# EfBox_v1.net
KiCad netlist of a schematic drawn in EAGLE
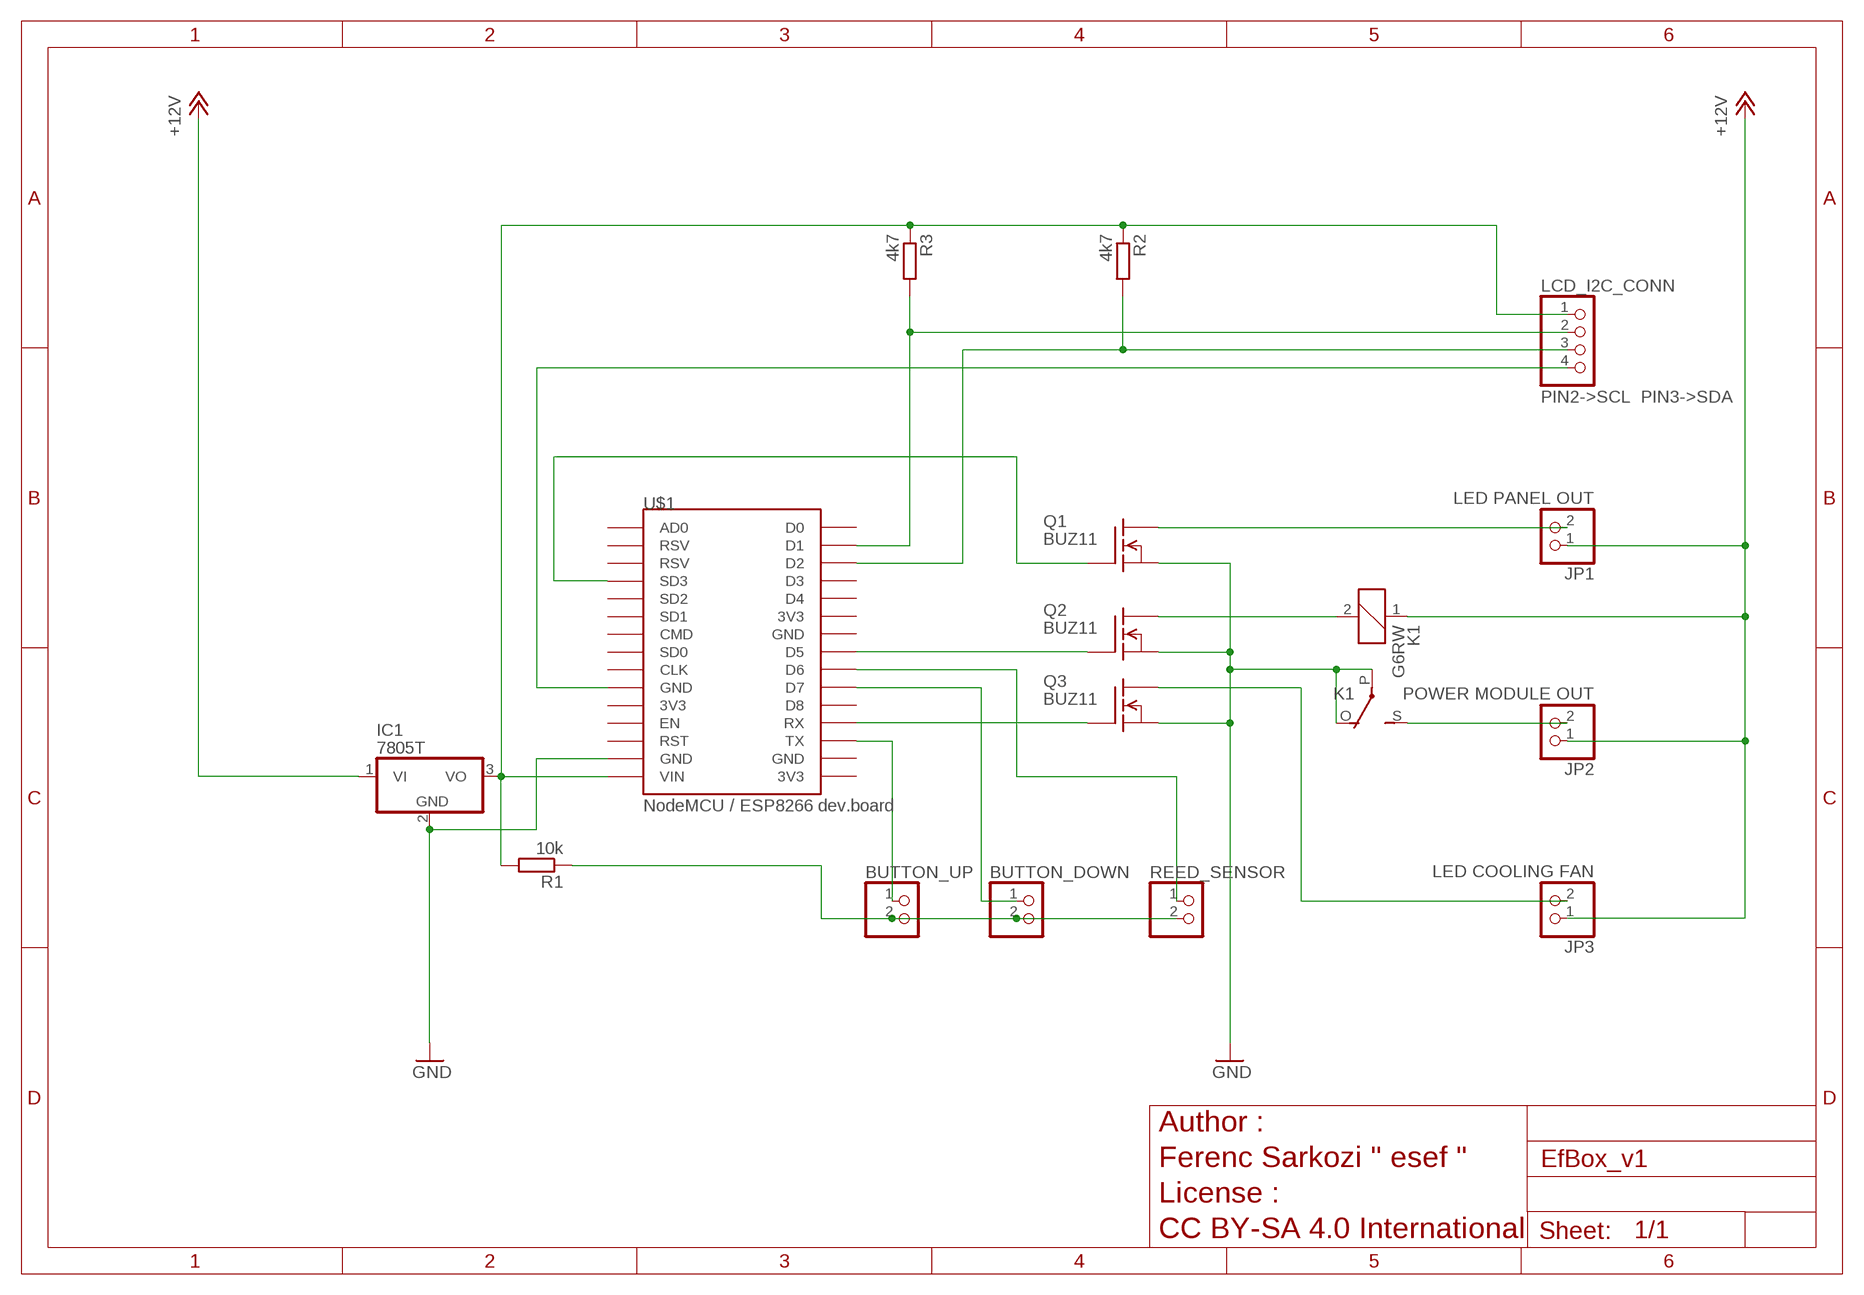
[diagram p0: schematic, sheet 1]

(export (version "E")
  (design (tool "Eeschema 10.0.6"))
  (components
    (comp (ref "BUTTON_DOWN")
      (value "PINHD-1X2")
      (footprint "eagle-import:1X02")
      (libsource (lib "eagle-import") (part "PINHD-1X2"))
    )
    (comp (ref "BUTTON_UP")
      (value "PINHD-1X2")
      (footprint "eagle-import:1X02")
      (libsource (lib "eagle-import") (part "PINHD-1X2"))
    )
    (comp (ref "IC1")
      (value "7805T")
      (footprint "eagle-import:TO220H")
      (libsource (lib "eagle-import") (part "78T05"))
    )
    (comp (ref "JP1")
      (value "LED PANEL OUT")
      (footprint "eagle-import:1X02")
      (libsource (lib "eagle-import") (part "PINHD-1X2"))
    )
    (comp (ref "JP2")
      (value "POWER MODULE OUT")
      (footprint "eagle-import:1X02")
      (libsource (lib "eagle-import") (part "PINHD-1X2"))
    )
    (comp (ref "JP3")
      (value "LED COOLING FAN")
      (footprint "eagle-import:1X02")
      (libsource (lib "eagle-import") (part "PINHD-1X2"))
    )
    (comp (ref "K1")
      (value "G6RW")
      (footprint "eagle-import:G6RW")
      (libsource (lib "eagle-import") (part "G6RW"))
    )
    (comp (ref "LCD_I2C_CONN")
      (value "PIN2->SCL PIN3->SDA")
      (footprint "eagle-import:1X04")
      (libsource (lib "eagle-import") (part "PINHD-1X4"))
    )
    (comp (ref "Q1")
      (value "BUZ11")
      (footprint "eagle-import:TO220")
      (libsource (lib "eagle-import") (part "BUZ11"))
    )
    (comp (ref "Q2")
      (value "BUZ11")
      (footprint "eagle-import:TO220")
      (libsource (lib "eagle-import") (part "BUZ11"))
    )
    (comp (ref "Q3")
      (value "BUZ11")
      (footprint "eagle-import:TO220")
      (libsource (lib "eagle-import") (part "BUZ11"))
    )
    (comp (ref "R1")
      (value "10k")
      (footprint "eagle-import:0411_12")
      (libsource (lib "eagle-import") (part "R-EU_0411/12"))
    )
    (comp (ref "R2")
      (value "4k7")
      (footprint "eagle-import:0411_12")
      (libsource (lib "eagle-import") (part "R-EU_0411/12"))
    )
    (comp (ref "R3")
      (value "4k7")
      (footprint "eagle-import:0411_12")
      (libsource (lib "eagle-import") (part "R-EU_0411/12"))
    )
    (comp (ref "REED_SENSOR")
      (value "PINHD-1X2")
      (footprint "eagle-import:1X02")
      (libsource (lib "eagle-import") (part "PINHD-1X2"))
    )
    (comp (ref "U$1")
      (value "NodeMCU / ESP8266 dev.board")
      (footprint "eagle-import:ESP12E_DEVKIT")
      (libsource (lib "eagle-import") (part "ESP12E_DEVKIT"))
    )
  )
  (nets
    (net (code "1") (name "+12V") (class "Default")
      (node (ref "IC1") (pin "1") (pinfunction "VI_1") (pintype "input"))
      (node (ref "JP1") (pin "1") (pinfunction "1_1") (pintype "passive"))
      (node (ref "JP2") (pin "1") (pinfunction "1_1") (pintype "passive"))
      (node (ref "JP3") (pin "1") (pinfunction "1_1") (pintype "passive"))
      (node (ref "K1") (pin "1") (pinfunction "1_1") (pintype "passive"))
    )
    (net (code "2") (name "GND") (class "Default")
      (node (ref "IC1") (pin "2") (pinfunction "GND_2") (pintype "passive"))
      (node (ref "K1") (pin "O") (pinfunction "O_O") (pintype "passive"))
      (node (ref "K1") (pin "P") (pinfunction "P_P") (pintype "passive"))
      (node (ref "Q1") (pin "3") (pinfunction "S_3") (pintype "passive"))
      (node (ref "Q2") (pin "3") (pinfunction "S_3") (pintype "passive"))
      (node (ref "Q3") (pin "3") (pinfunction "S_3") (pintype "passive"))
      (node (ref "U$1") (pin "GND@1") (pinfunction "GND_GND@1") (pintype "bidirectional"))
    )
    (net (code "3") (name "Net-(BUTTON_DOWN-Pad1)") (class "Default")
      (node (ref "BUTTON_DOWN") (pin "1") (pinfunction "1_1") (pintype "passive"))
      (node (ref "U$1") (pin "D7") (pinfunction "D7_D7") (pintype "bidirectional"))
    )
    (net (code "4") (name "Net-(BUTTON_DOWN-Pad2)") (class "Default")
      (node (ref "BUTTON_DOWN") (pin "2") (pinfunction "2_2") (pintype "passive"))
      (node (ref "BUTTON_UP") (pin "2") (pinfunction "2_2") (pintype "passive"))
      (node (ref "R1") (pin "1") (pinfunction "1_1") (pintype "passive"))
      (node (ref "REED_SENSOR") (pin "2") (pinfunction "2_2") (pintype "passive"))
    )
    (net (code "5") (name "Net-(BUTTON_UP-Pad1)") (class "Default")
      (node (ref "BUTTON_UP") (pin "1") (pinfunction "1_1") (pintype "passive"))
      (node (ref "U$1") (pin "TX") (pinfunction "TX_TX") (pintype "bidirectional"))
    )
    (net (code "6") (name "Net-(IC1-VO)") (class "Default")
      (node (ref "IC1") (pin "3") (pinfunction "VO_3") (pintype "passive"))
      (node (ref "LCD_I2C_CONN") (pin "1") (pinfunction "1_1") (pintype "passive"))
      (node (ref "R1") (pin "2") (pinfunction "2_2") (pintype "passive"))
      (node (ref "R2") (pin "1") (pinfunction "1_1") (pintype "passive"))
      (node (ref "R3") (pin "1") (pinfunction "1_1") (pintype "passive"))
      (node (ref "U$1") (pin "VIN") (pinfunction "VIN_VIN") (pintype "bidirectional"))
    )
    (net (code "7") (name "Net-(JP2-Pad2)") (class "Default")
      (node (ref "JP2") (pin "2") (pinfunction "2_2") (pintype "passive"))
      (node (ref "K1") (pin "S") (pinfunction "S_S") (pintype "passive"))
    )
    (net (code "8") (name "Net-(LCD_I2C_CONN-Pad2)") (class "Default")
      (node (ref "LCD_I2C_CONN") (pin "2") (pinfunction "2_2") (pintype "passive"))
      (node (ref "R3") (pin "2") (pinfunction "2_2") (pintype "passive"))
      (node (ref "U$1") (pin "D1") (pinfunction "D1_D1") (pintype "bidirectional"))
    )
    (net (code "9") (name "Net-(LCD_I2C_CONN-Pad3)") (class "Default")
      (node (ref "LCD_I2C_CONN") (pin "3") (pinfunction "3_3") (pintype "passive"))
      (node (ref "R2") (pin "2") (pinfunction "2_2") (pintype "passive"))
      (node (ref "U$1") (pin "D2") (pinfunction "D2_D2") (pintype "bidirectional"))
    )
    (net (code "10") (name "Net-(LCD_I2C_CONN-Pad4)") (class "Default")
      (node (ref "LCD_I2C_CONN") (pin "4") (pinfunction "4_4") (pintype "passive"))
      (node (ref "U$1") (pin "GND@0") (pinfunction "GND_GND@0") (pintype "bidirectional"))
    )
    (net (code "11") (name "Net-(Q1-D)") (class "Default")
      (node (ref "JP1") (pin "2") (pinfunction "2_2") (pintype "passive"))
      (node (ref "Q1") (pin "2") (pinfunction "D_2") (pintype "passive"))
    )
    (net (code "12") (name "Net-(Q1-G)") (class "Default")
      (node (ref "Q1") (pin "1") (pinfunction "G_1") (pintype "passive"))
      (node (ref "U$1") (pin "SD3") (pinfunction "SD3_SD3") (pintype "bidirectional"))
    )
    (net (code "13") (name "Net-(Q2-D)") (class "Default")
      (node (ref "K1") (pin "2") (pinfunction "2_2") (pintype "passive"))
      (node (ref "Q2") (pin "2") (pinfunction "D_2") (pintype "passive"))
    )
    (net (code "14") (name "Net-(Q2-G)") (class "Default")
      (node (ref "Q2") (pin "1") (pinfunction "G_1") (pintype "passive"))
      (node (ref "U$1") (pin "D5") (pinfunction "D5_D5") (pintype "bidirectional"))
    )
    (net (code "15") (name "Net-(Q3-D)") (class "Default")
      (node (ref "JP3") (pin "2") (pinfunction "2_2") (pintype "passive"))
      (node (ref "Q3") (pin "2") (pinfunction "D_2") (pintype "passive"))
    )
    (net (code "16") (name "Net-(Q3-G)") (class "Default")
      (node (ref "Q3") (pin "1") (pinfunction "G_1") (pintype "passive"))
      (node (ref "U$1") (pin "RX") (pinfunction "RX_RX") (pintype "bidirectional"))
    )
    (net (code "17") (name "Net-(REED_SENSOR-Pad1)") (class "Default")
      (node (ref "REED_SENSOR") (pin "1") (pinfunction "1_1") (pintype "passive"))
      (node (ref "U$1") (pin "D6") (pinfunction "D6_D6") (pintype "bidirectional"))
    )
    (net (code "18") (name "unconnected-(U$1-3V3-Pad3V3@0)") (class "Default")
      (node (ref "U$1") (pin "3V3@0") (pinfunction "3V3_3V3@0") (pintype "bidirectional"))
    )
    (net (code "19") (name "unconnected-(U$1-3V3-Pad3V3@1)") (class "Default")
      (node (ref "U$1") (pin "3V3@1") (pinfunction "3V3_3V3@1") (pintype "bidirectional"))
    )
    (net (code "20") (name "unconnected-(U$1-3V3-Pad3V3@2)") (class "Default")
      (node (ref "U$1") (pin "3V3@2") (pinfunction "3V3_3V3@2") (pintype "bidirectional"))
    )
    (net (code "21") (name "unconnected-(U$1-GND-PadGND@2)") (class "Default")
      (node (ref "U$1") (pin "GND@2") (pinfunction "GND_GND@2") (pintype "bidirectional"))
    )
    (net (code "22") (name "unconnected-(U$1-GND-PadGND@3)") (class "Default")
      (node (ref "U$1") (pin "GND@3") (pinfunction "GND_GND@3") (pintype "bidirectional"))
    )
    (net (code "23") (name "unconnected-(U$1-PadAD0)") (class "Default")
      (node (ref "U$1") (pin "AD0") (pinfunction "AD0_AD0") (pintype "bidirectional"))
    )
    (net (code "24") (name "unconnected-(U$1-PadCLK)") (class "Default")
      (node (ref "U$1") (pin "CLK") (pinfunction "CLK_CLK") (pintype "bidirectional"))
    )
    (net (code "25") (name "unconnected-(U$1-PadCMD)") (class "Default")
      (node (ref "U$1") (pin "CMD") (pinfunction "CMD_CMD") (pintype "bidirectional"))
    )
    (net (code "26") (name "unconnected-(U$1-PadD0)") (class "Default")
      (node (ref "U$1") (pin "D0") (pinfunction "D0_D0") (pintype "bidirectional"))
    )
    (net (code "27") (name "unconnected-(U$1-PadD3)") (class "Default")
      (node (ref "U$1") (pin "D3") (pinfunction "D3_D3") (pintype "bidirectional"))
    )
    (net (code "28") (name "unconnected-(U$1-PadD4)") (class "Default")
      (node (ref "U$1") (pin "D4") (pinfunction "D4_D4") (pintype "bidirectional"))
    )
    (net (code "29") (name "unconnected-(U$1-PadD8)") (class "Default")
      (node (ref "U$1") (pin "D8") (pinfunction "D8_D8") (pintype "bidirectional"))
    )
    (net (code "30") (name "unconnected-(U$1-PadEN)") (class "Default")
      (node (ref "U$1") (pin "EN") (pinfunction "EN_EN") (pintype "bidirectional"))
    )
    (net (code "31") (name "unconnected-(U$1-PadRST)") (class "Default")
      (node (ref "U$1") (pin "RST") (pinfunction "RST_RST") (pintype "bidirectional"))
    )
    (net (code "32") (name "unconnected-(U$1-PadSD0)") (class "Default")
      (node (ref "U$1") (pin "SD0") (pinfunction "SD0_SD0") (pintype "bidirectional"))
    )
    (net (code "33") (name "unconnected-(U$1-PadSD1)") (class "Default")
      (node (ref "U$1") (pin "SD1") (pinfunction "SD1_SD1") (pintype "bidirectional"))
    )
    (net (code "34") (name "unconnected-(U$1-PadSD2)") (class "Default")
      (node (ref "U$1") (pin "SD2") (pinfunction "SD2_SD2") (pintype "bidirectional"))
    )
    (net (code "35") (name "unconnected-(U$1-RSV-PadRSV@0)") (class "Default")
      (node (ref "U$1") (pin "RSV@0") (pinfunction "RSV_RSV@0") (pintype "bidirectional"))
    )
    (net (code "36") (name "unconnected-(U$1-RSV-PadRSV@1)") (class "Default")
      (node (ref "U$1") (pin "RSV@1") (pinfunction "RSV_RSV@1") (pintype "bidirectional"))
    )
  )
)
